# 02_ESP12.net
KiCad netlist of a schematic drawn in Altium Designer
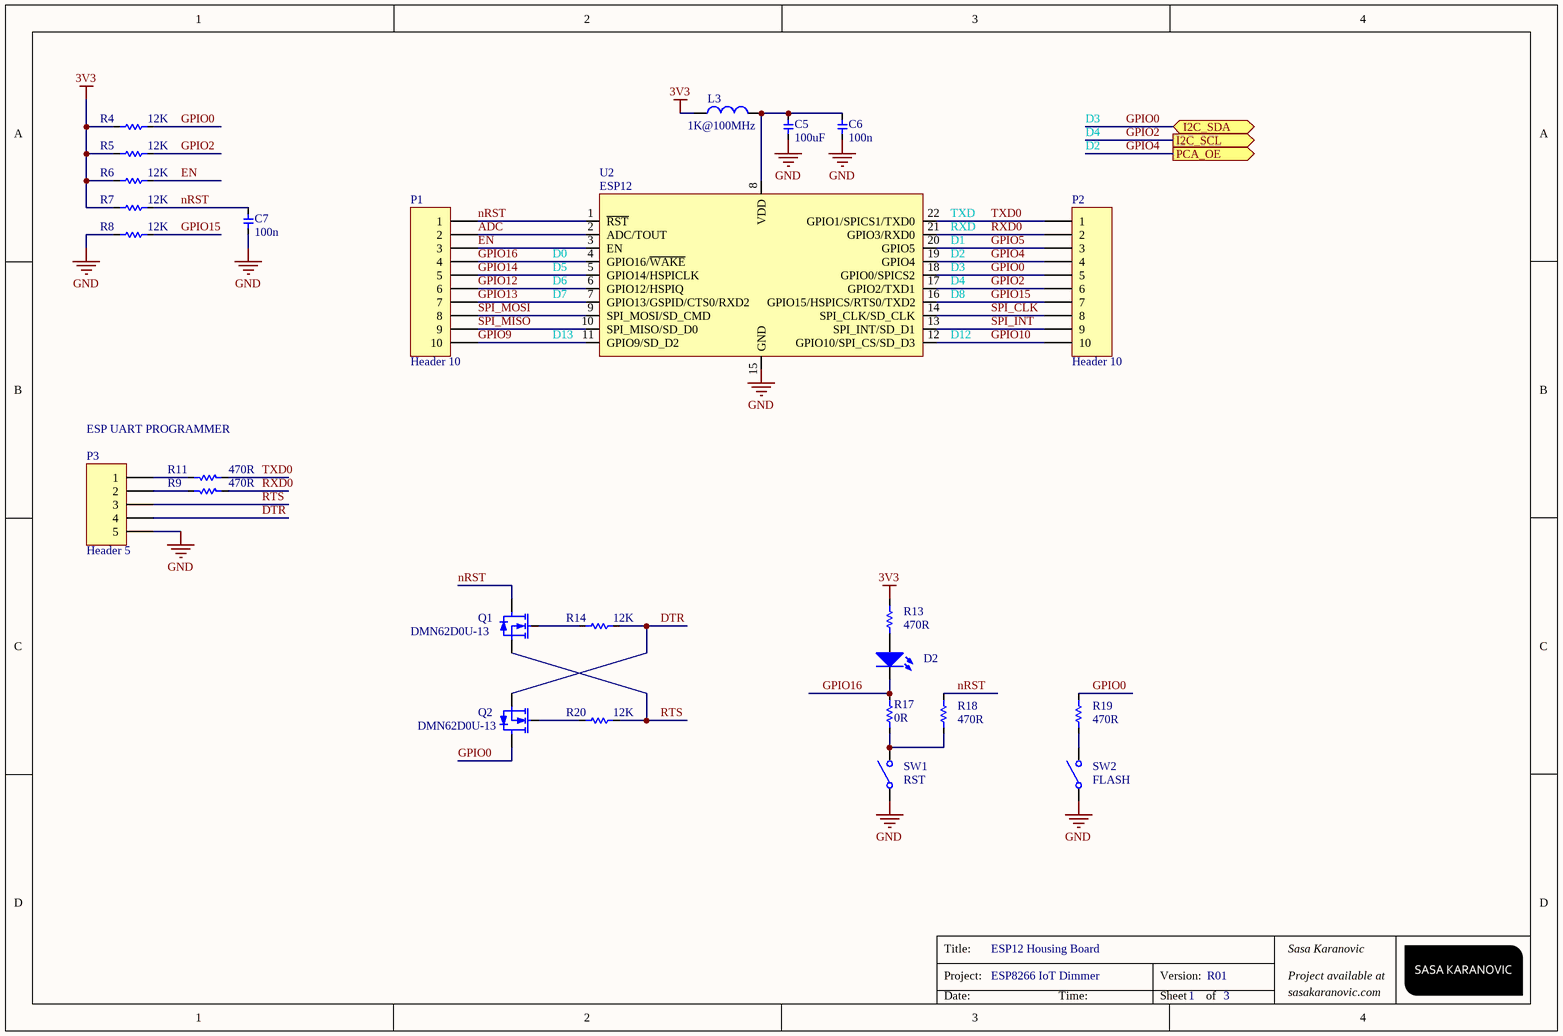
[diagram p0: 02_ESP12.SchDoc]

(export (version "E")
  (design (tool "Eeschema 10.0.6"))
  (components
    (comp (ref "C5")
      (value "100uF")
      (footprint "Moji Footprintovi:CAPC_1411_3528_X08N")
      (description "Capacitor")
      (fields
        (field (name "MANUFACTURER") "AVX Corporation")
        (field (name "MANUFACTURER PART NUMBER") "TAJB107M006RNJ")
      )
      (libsource (lib "Moji Schematici") (part "Cap"))
    )
    (comp (ref "C6")
      (value "100n")
      (footprint "Moji Footprintovi:0603 - CAP")
      (description "Capacitor")
      (fields
        (field (name "MANUFACTURER") "AVX Corporation")
        (field (name "MANUFACTURER PART NUMBER") "06035C104KAT2A")
      )
      (libsource (lib "Moji Schematici") (part "Cap"))
    )
    (comp (ref "C7")
      (value "100n")
      (footprint "Moji Footprintovi:0603 - CAP")
      (description "Capacitor")
      (fields
        (field (name "MANUFACTURER") "AVX Corporation")
        (field (name "MANUFACTURER PART NUMBER") "06035C104KAT2A")
      )
      (libsource (lib "Moji Schematici") (part "Cap"))
    )
    (comp (ref "D2")
      (value "LED")
      (footprint "Moji Footprintovi:0603 Diode")
      (description "Typical RED GaAs LED")
      (fields
        (field (name "DISTRIBUTOR PART NUMBER") "160-1830-1-ND")
        (field (name "MANUFACTURER") "Lite-On Inc.")
      )
      (libsource (lib "Moji Schematici") (part "LED"))
    )
    (comp (ref "L3")
      (value "1K@100MHz")
      (footprint "Moji Footprintovi:0603")
      (description "FERRITE BEAD 1 KOHM 0603 1LN")
      (fields
        (field (name "MANUFACTURER") "TDK Corporation")
        (field (name "MANUFACTURER PART NUMBER") "MPZ1608S102ATA00")
      )
      (libsource (lib "Moji Schematici") (part "Inductor"))
    )
    (comp (ref "P1")
      (value "Header 10")
      (footprint "HDR1X10")
      (description "Header, 10-Pin")
      (fields
        (field (name "DISTRIBUTOR PART NUMBER") "952-1843-ND")
        (field (name "MANUFACTURER") "Harwin Inc.")
      )
      (libsource (lib "") (part "Header 10_1"))
    )
    (comp (ref "P2")
      (value "Header 10")
      (footprint "HDR1X10")
      (description "Header, 10-Pin")
      (fields
        (field (name "DISTRIBUTOR PART NUMBER") "952-1843-ND")
        (field (name "MANUFACTURER") "Harwin Inc.")
      )
      (libsource (lib "Moji Schematici") (part "Header 10"))
    )
    (comp (ref "P3")
      (value "Header 5")
      (footprint "Moji Footprintovi:Header 5x1")
      (description "SIL VERTICAL PC TAIL PIN HEADER")
      (fields
        (field (name "MANUFACTURER") "Harwin Inc.")
        (field (name "MANUFACTURER PART NUMBER") "M20-9990546")
      )
      (libsource (lib "Moji Schematici") (part "Header 5"))
    )
    (comp (ref "Q1")
      (value "DMN62D0U-13")
      (footprint "Moji Footprintovi:SOT90P240X100-3N")
      (description "MOSFET N-CH 60V 0.38A")
      (fields
        (field (name "MANUFACTURER") "Diodes Incorporated")
        (field (name "DISTRIBUTOR PART NUMBER") "DMN62D0U-13DICT-ND")
      )
      (libsource (lib "Moji Schematici") (part "DMN62D0U-13"))
    )
    (comp (ref "Q2")
      (value "DMN62D0U-13")
      (footprint "Moji Footprintovi:SOT90P240X100-3N")
      (description "MOSFET N-CH 60V 0.38A")
      (fields
        (field (name "MANUFACTURER") "Diodes Incorporated")
        (field (name "DISTRIBUTOR PART NUMBER") "DMN62D0U-13DICT-ND")
      )
      (libsource (lib "Moji Schematici") (part "DMN62D0U-13"))
    )
    (comp (ref "R4")
      (value "12K")
      (footprint "Moji Footprintovi:0603")
      (description "Resistor")
      (fields
        (field (name "MANUFACTURER") "Yageo")
        (field (name "MANUFACTURER PART NUMBER") "RT0603FRE0712KL")
      )
      (libsource (lib "Moji Schematici") (part "Res"))
    )
    (comp (ref "R5")
      (value "12K")
      (footprint "Moji Footprintovi:0603")
      (description "Resistor")
      (fields
        (field (name "MANUFACTURER") "Yageo")
        (field (name "MANUFACTURER PART NUMBER") "RT0603FRE0712KL")
      )
      (libsource (lib "Moji Schematici") (part "Res"))
    )
    (comp (ref "R6")
      (value "12K")
      (footprint "Moji Footprintovi:0603")
      (description "Resistor")
      (fields
        (field (name "MANUFACTURER") "Yageo")
        (field (name "MANUFACTURER PART NUMBER") "RT0603FRE0712KL")
      )
      (libsource (lib "Moji Schematici") (part "Res"))
    )
    (comp (ref "R7")
      (value "12K")
      (footprint "Moji Footprintovi:0603")
      (description "Resistor")
      (fields
        (field (name "MANUFACTURER") "Yageo")
        (field (name "MANUFACTURER PART NUMBER") "RT0603FRE0712KL")
      )
      (libsource (lib "Moji Schematici") (part "Res"))
    )
    (comp (ref "R8")
      (value "12K")
      (footprint "Moji Footprintovi:0603")
      (description "Resistor")
      (fields
        (field (name "MANUFACTURER") "Yageo")
        (field (name "MANUFACTURER PART NUMBER") "RT0603FRE0712KL")
      )
      (libsource (lib "Moji Schematici") (part "Res"))
    )
    (comp (ref "R9")
      (value "470R")
      (footprint "Moji Footprintovi:0603")
      (description "Resistor")
      (fields
        (field (name "MANUFACTURER") "Yageo")
        (field (name "MANUFACTURER PART NUMBER") "AC0603FR-07470RL")
      )
      (libsource (lib "Moji Schematici") (part "Res"))
    )
    (comp (ref "R11")
      (value "470R")
      (footprint "Moji Footprintovi:0603")
      (description "Resistor")
      (fields
        (field (name "MANUFACTURER") "Yageo")
        (field (name "MANUFACTURER PART NUMBER") "AC0603FR-07470RL")
      )
      (libsource (lib "Moji Schematici") (part "Res"))
    )
    (comp (ref "R13")
      (value "470R")
      (footprint "Moji Footprintovi:0603")
      (description "Resistor")
      (fields
        (field (name "MANUFACTURER") "Yageo")
        (field (name "MANUFACTURER PART NUMBER") "AC0603FR-07470RL")
      )
      (libsource (lib "Moji Schematici") (part "Res"))
    )
    (comp (ref "R14")
      (value "12K")
      (footprint "Moji Footprintovi:0603")
      (description "Resistor")
      (fields
        (field (name "MANUFACTURER") "Yageo")
        (field (name "MANUFACTURER PART NUMBER") "RT0603FRE0712KL")
      )
      (libsource (lib "Moji Schematici") (part "Res"))
    )
    (comp (ref "R17")
      (value "0R")
      (footprint "Moji Footprintovi:0603")
      (description "Resistor")
      (fields
        (field (name "MANUFACTURER") "Yageo")
        (field (name "MANUFACTURER PART NUMBER") "RC0603JR-070RL")
      )
      (libsource (lib "Moji Schematici") (part "Res"))
    )
    (comp (ref "R18")
      (value "470R")
      (footprint "Moji Footprintovi:0603")
      (description "Resistor")
      (fields
        (field (name "MANUFACTURER") "Yageo")
        (field (name "MANUFACTURER PART NUMBER") "AC0603FR-07470RL")
      )
      (libsource (lib "Moji Schematici") (part "Res"))
    )
    (comp (ref "R19")
      (value "470R")
      (footprint "Moji Footprintovi:0603")
      (description "Resistor")
      (fields
        (field (name "MANUFACTURER") "Yageo")
        (field (name "MANUFACTURER PART NUMBER") "AC0603FR-07470RL")
      )
      (libsource (lib "Moji Schematici") (part "Res"))
    )
    (comp (ref "R20")
      (value "12K")
      (footprint "Moji Footprintovi:0603")
      (description "Resistor")
      (fields
        (field (name "MANUFACTURER") "Yageo")
        (field (name "MANUFACTURER PART NUMBER") "RT0603FRE0712KL")
      )
      (libsource (lib "Moji Schematici") (part "Res"))
    )
    (comp (ref "SW1")
      (value "Switch")
      (footprint "SMD Switch 2pin")
      (fields
        (field (name "DISTRIBUTOR PART NUMBER") "952-1843-ND")
        (field (name "MANUFACTURER") "Harwin Inc.")
        (field (name "MANUFACTURER PART NUMBER") "M20-9991046")
      )
      (libsource (lib "Moji Schematici") (part "Switch"))
    )
    (comp (ref "SW2")
      (value "Switch")
      (footprint "SMD Switch 2pin")
      (fields
        (field (name "DISTRIBUTOR PART NUMBER") "952-1843-ND")
        (field (name "MANUFACTURER") "Harwin Inc.")
        (field (name "MANUFACTURER PART NUMBER") "M20-9991046")
      )
      (libsource (lib "Moji Schematici") (part "Switch"))
    )
    (comp (ref "U2")
      (value "ESP12")
      (footprint "Moji Footprintovi:ESP-12")
      (description "ESP8266 SMT Module - ESP-12S")
      (fields
        (field (name "MANUFACTURER") "Seeed Technology Co., Ltd")
        (field (name "MANUFACTURER PART NUMBER") "317060015")
      )
      (libsource (lib "Moji Schematici") (part "ESP12"))
    )
  )
  (nets
    (net (code "1") (name "/ADC") (class "Default")
      (node (ref "P1") (pin "2") (pinfunction "2_2") (pintype "passive"))
      (node (ref "U2") (pin "2") (pinfunction "ADC/TOUT_2") (pintype "passive"))
    )
    (net (code "2") (name "/DTR") (class "Default")
      (node (ref "P3") (pin "4") (pinfunction "4_4") (pintype "passive"))
      (node (ref "Q2") (pin "3") (pinfunction "S_3") (pintype "passive"))
      (node (ref "R14") (pin "2") (pinfunction "2_2") (pintype "passive"))
    )
    (net (code "3") (name "/EN") (class "Default")
      (node (ref "P1") (pin "3") (pinfunction "3_3") (pintype "passive"))
      (node (ref "R6") (pin "2") (pinfunction "2_2") (pintype "passive"))
      (node (ref "U2") (pin "3") (pinfunction "EN_3") (pintype "passive"))
    )
    (net (code "4") (name "/GPIO0") (class "Default")
      (node (ref "P2") (pin "5") (pinfunction "5_5") (pintype "passive"))
      (node (ref "Q2") (pin "2") (pinfunction "D_2") (pintype "passive"))
      (node (ref "R19") (pin "2") (pinfunction "2_2") (pintype "passive"))
      (node (ref "R4") (pin "2") (pinfunction "2_2") (pintype "passive"))
      (node (ref "U2") (pin "18") (pinfunction "GPIO0/SPICS2_18") (pintype "passive"))
    )
    (net (code "5") (name "/GPIO2") (class "Default")
      (node (ref "P2") (pin "6") (pinfunction "6_6") (pintype "passive"))
      (node (ref "R5") (pin "2") (pinfunction "2_2") (pintype "passive"))
      (node (ref "U2") (pin "17") (pinfunction "GPIO2/TXD1_17") (pintype "passive"))
    )
    (net (code "6") (name "/GPIO4") (class "Default")
      (node (ref "P2") (pin "4") (pinfunction "4_4") (pintype "passive"))
      (node (ref "U2") (pin "19") (pinfunction "GPIO4_19") (pintype "passive"))
    )
    (net (code "7") (name "/GPIO5") (class "Default")
      (node (ref "P2") (pin "3") (pinfunction "3_3") (pintype "passive"))
      (node (ref "U2") (pin "20") (pinfunction "GPIO5_20") (pintype "passive"))
    )
    (net (code "8") (name "/GPIO9") (class "Default")
      (node (ref "P1") (pin "10") (pinfunction "10_10") (pintype "passive"))
      (node (ref "U2") (pin "11") (pinfunction "GPIO9/SD_D2_11") (pintype "passive"))
    )
    (net (code "9") (name "/GPIO10") (class "Default")
      (node (ref "P2") (pin "10") (pinfunction "10_10") (pintype "passive"))
      (node (ref "U2") (pin "12") (pinfunction "GPIO10/SPI_CS/SD_D3_12") (pintype "passive"))
    )
    (net (code "10") (name "/GPIO12") (class "Default")
      (node (ref "P1") (pin "6") (pinfunction "6_6") (pintype "passive"))
      (node (ref "U2") (pin "6") (pinfunction "GPIO12/HSPIQ_6") (pintype "passive"))
    )
    (net (code "11") (name "/GPIO13") (class "Default")
      (node (ref "P1") (pin "7") (pinfunction "7_7") (pintype "passive"))
      (node (ref "U2") (pin "7") (pinfunction "GPIO13/GSPID/CTS0/RXD2_7") (pintype "passive"))
    )
    (net (code "12") (name "/GPIO14") (class "Default")
      (node (ref "P1") (pin "5") (pinfunction "5_5") (pintype "passive"))
      (node (ref "U2") (pin "5") (pinfunction "GPIO14/HSPICLK_5") (pintype "passive"))
    )
    (net (code "13") (name "/GPIO15") (class "Default")
      (node (ref "P2") (pin "7") (pinfunction "7_7") (pintype "passive"))
      (node (ref "R8") (pin "2") (pinfunction "2_2") (pintype "passive"))
      (node (ref "U2") (pin "16") (pinfunction "GPIO15/HSPICS/RTS0/TXD2_16") (pintype "passive"))
    )
    (net (code "14") (name "/GPIO16") (class "Default")
      (node (ref "D2") (pin "K") (pinfunction "K_K") (pintype "passive"))
      (node (ref "P1") (pin "4") (pinfunction "4_4") (pintype "passive"))
      (node (ref "R17") (pin "1") (pinfunction "1_1") (pintype "passive"))
      (node (ref "U2") (pin "4") (pinfunction "GPIO16/~{WAKE}_4") (pintype "passive"))
    )
    (net (code "15") (name "/RTS") (class "Default")
      (node (ref "P3") (pin "3") (pinfunction "3_3") (pintype "passive"))
      (node (ref "Q1") (pin "3") (pinfunction "S_3") (pintype "passive"))
      (node (ref "R20") (pin "2") (pinfunction "2_2") (pintype "passive"))
    )
    (net (code "16") (name "/RXD0") (class "Default")
      (node (ref "P2") (pin "2") (pinfunction "2_2") (pintype "passive"))
      (node (ref "R9") (pin "2") (pinfunction "2_2") (pintype "passive"))
      (node (ref "U2") (pin "21") (pinfunction "GPIO3/RXD0_21") (pintype "passive"))
    )
    (net (code "17") (name "/SPI_CLK") (class "Default")
      (node (ref "P2") (pin "8") (pinfunction "8_8") (pintype "passive"))
      (node (ref "U2") (pin "14") (pinfunction "SPI_CLK/SD_CLK_14") (pintype "passive"))
    )
    (net (code "18") (name "/SPI_INT") (class "Default")
      (node (ref "P2") (pin "9") (pinfunction "9_9") (pintype "passive"))
      (node (ref "U2") (pin "13") (pinfunction "SPI_INT/SD_D1_13") (pintype "passive"))
    )
    (net (code "19") (name "/SPI_MISO") (class "Default")
      (node (ref "P1") (pin "9") (pinfunction "9_9") (pintype "passive"))
      (node (ref "U2") (pin "10") (pinfunction "SPI_MISO/SD_D0_10") (pintype "passive"))
    )
    (net (code "20") (name "/SPI_MOSI") (class "Default")
      (node (ref "P1") (pin "8") (pinfunction "8_8") (pintype "passive"))
      (node (ref "U2") (pin "9") (pinfunction "SPI_MOSI/SD_CMD_9") (pintype "passive"))
    )
    (net (code "21") (name "/TXD0") (class "Default")
      (node (ref "P2") (pin "1") (pinfunction "1_1") (pintype "passive"))
      (node (ref "R11") (pin "2") (pinfunction "2_2") (pintype "passive"))
      (node (ref "U2") (pin "22") (pinfunction "GPIO1/SPICS1/TXD0_22") (pintype "passive"))
    )
    (net (code "22") (name "/nRST") (class "Default")
      (node (ref "C7") (pin "2") (pinfunction "2_2") (pintype "passive"))
      (node (ref "P1") (pin "1") (pinfunction "1_1") (pintype "passive"))
      (node (ref "Q1") (pin "2") (pinfunction "D_2") (pintype "passive"))
      (node (ref "R18") (pin "2") (pinfunction "2_2") (pintype "passive"))
      (node (ref "R7") (pin "2") (pinfunction "2_2") (pintype "passive"))
      (node (ref "U2") (pin "1") (pinfunction "~{RST}_1") (pintype "passive"))
    )
    (net (code "23") (name "3V3") (class "Default")
      (node (ref "L3") (pin "1") (pinfunction "1_1") (pintype "passive"))
      (node (ref "R13") (pin "2") (pinfunction "2_2") (pintype "passive"))
      (node (ref "R4") (pin "1") (pinfunction "1_1") (pintype "passive"))
      (node (ref "R5") (pin "1") (pinfunction "1_1") (pintype "passive"))
      (node (ref "R6") (pin "1") (pinfunction "1_1") (pintype "passive"))
      (node (ref "R7") (pin "1") (pinfunction "1_1") (pintype "passive"))
    )
    (net (code "24") (name "GND") (class "Default")
      (node (ref "C5") (pin "1") (pinfunction "1_1") (pintype "passive"))
      (node (ref "C6") (pin "1") (pinfunction "1_1") (pintype "passive"))
      (node (ref "C7") (pin "1") (pinfunction "1_1") (pintype "passive"))
      (node (ref "P3") (pin "5") (pinfunction "5_5") (pintype "passive"))
      (node (ref "R8") (pin "1") (pinfunction "1_1") (pintype "passive"))
      (node (ref "SW1") (pin "1") (pinfunction "COMMON1_1") (pintype "passive"))
      (node (ref "SW2") (pin "1") (pinfunction "COMMON1_1") (pintype "passive"))
      (node (ref "U2") (pin "15") (pinfunction "GND_15") (pintype "passive"))
    )
    (net (code "25") (name "Net-(D2-PadA)") (class "Default")
      (node (ref "D2") (pin "A") (pinfunction "A_A") (pintype "passive"))
      (node (ref "R13") (pin "1") (pinfunction "1_1") (pintype "passive"))
    )
    (net (code "26") (name "Net-(P3-Pad1)") (class "Default")
      (node (ref "P3") (pin "1") (pinfunction "1_1") (pintype "passive"))
      (node (ref "R11") (pin "1") (pinfunction "1_1") (pintype "passive"))
    )
    (net (code "27") (name "Net-(P3-Pad2)") (class "Default")
      (node (ref "P3") (pin "2") (pinfunction "2_2") (pintype "passive"))
      (node (ref "R9") (pin "1") (pinfunction "1_1") (pintype "passive"))
    )
    (net (code "28") (name "Net-(Q1-G)") (class "Default")
      (node (ref "Q1") (pin "1") (pinfunction "G_1") (pintype "passive"))
      (node (ref "R14") (pin "1") (pinfunction "1_1") (pintype "passive"))
    )
    (net (code "29") (name "Net-(Q2-G)") (class "Default")
      (node (ref "Q2") (pin "1") (pinfunction "G_1") (pintype "passive"))
      (node (ref "R20") (pin "1") (pinfunction "1_1") (pintype "passive"))
    )
    (net (code "30") (name "Net-(SW1-COMMON2)") (class "Default")
      (node (ref "R17") (pin "2") (pinfunction "2_2") (pintype "passive"))
      (node (ref "R18") (pin "1") (pinfunction "1_1") (pintype "passive"))
      (node (ref "SW1") (pin "2") (pinfunction "COMMON2_2") (pintype "passive"))
    )
    (net (code "31") (name "Net-(SW2-COMMON2)") (class "Default")
      (node (ref "R19") (pin "1") (pinfunction "1_1") (pintype "passive"))
      (node (ref "SW2") (pin "2") (pinfunction "COMMON2_2") (pintype "passive"))
    )
    (net (code "32") (name "Net-(U2-VDD)") (class "Default")
      (node (ref "C5") (pin "2") (pinfunction "2_2") (pintype "passive"))
      (node (ref "C6") (pin "2") (pinfunction "2_2") (pintype "passive"))
      (node (ref "L3") (pin "2") (pinfunction "2_2") (pintype "passive"))
      (node (ref "U2") (pin "8") (pinfunction "VDD_8") (pintype "passive"))
    )
  )
)
